# Candunio.net
KiCad netlist of a schematic drawn in Altium Designer
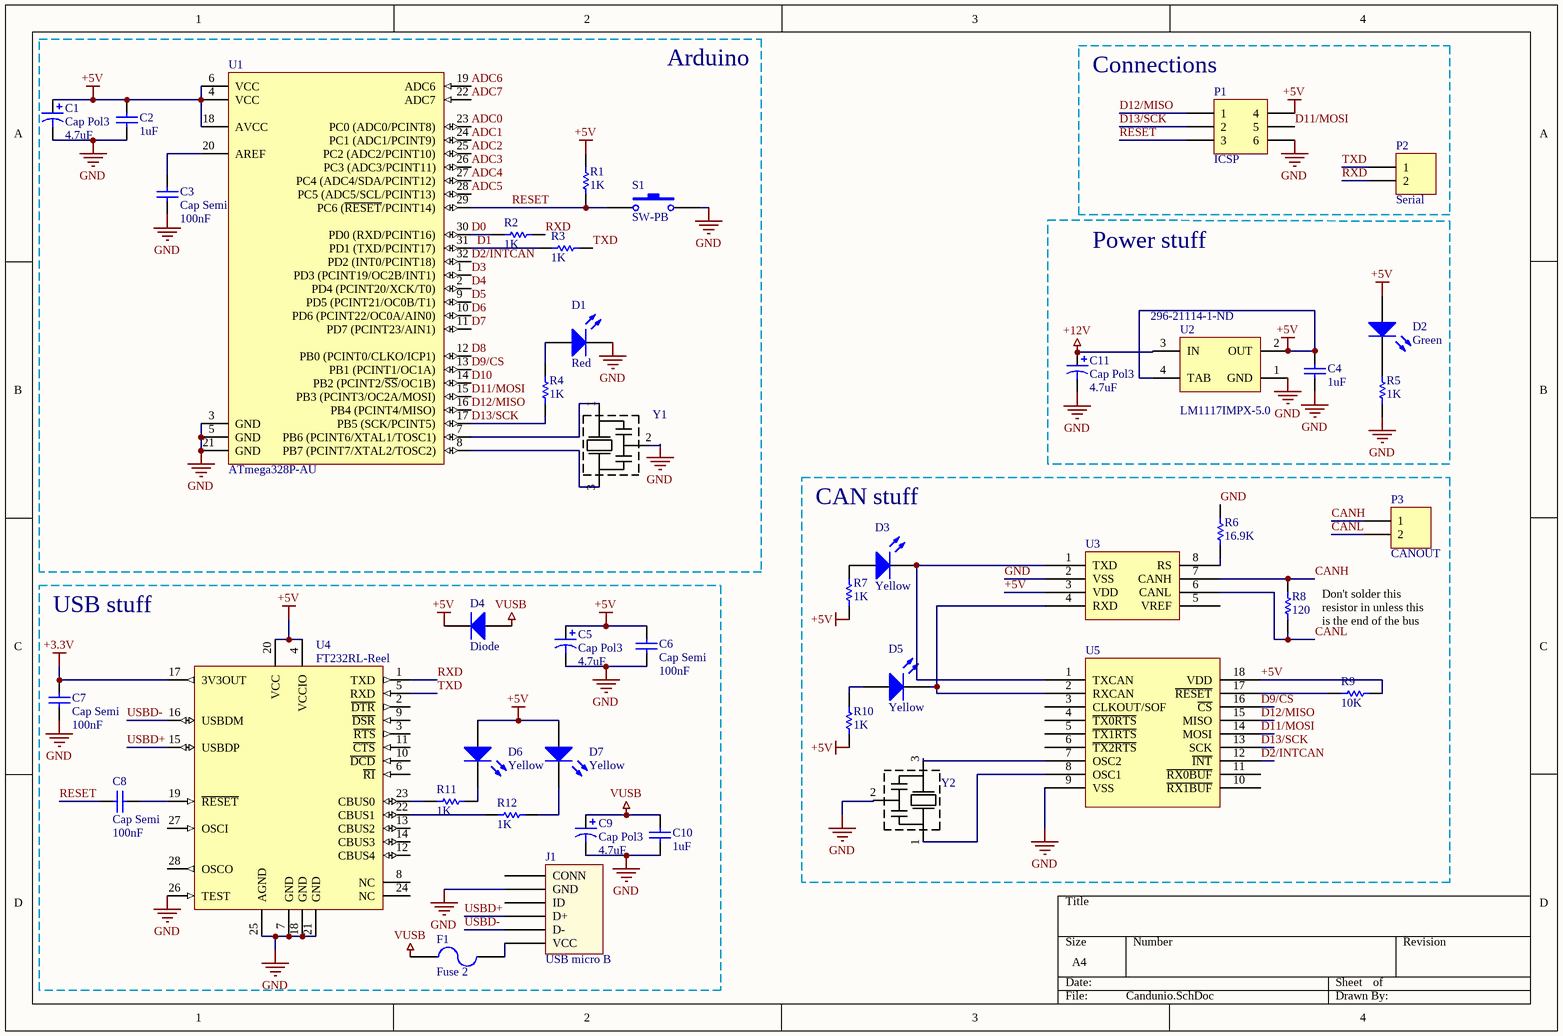
[diagram p0: Candunio.SchDoc]

(export (version "E")
  (design (tool "Eeschema 10.0.6"))
  (components
    (comp (ref "C1")
      (value "Cap Pol3")
      (footprint "CAPC3216X170N")
      (description "Polarized Capacitor (Surface Mount)")
      (fields
        (field (name "ALTIUM_VALUE") "4.7uF")
        (field (name "MANUFACTURER") "Kyocera AVX")
        (field (name "MANUFACTURER PART NUMBER") "12063C475KAT2A")
        (field (name "PUBLISHER") "Altium Limited")
      )
      (libsource (lib "Miscellaneous Devices") (part "Cap Pol3"))
    )
    (comp (ref "C2")
      (value "1uF")
      (footprint "CAPC3216X170N")
      (description "Capacitor (Semiconductor SIM Model)")
      (fields
        (field (name "MANUFACTURER") "Murata")
        (field (name "MANUFACTURER PART NUMBER") "GRM31MR71H105KA88L")
        (field (name "PUBLISHER") "Altium Limited")
      )
      (libsource (lib "Miscellaneous Devices") (part "Cap Semi"))
    )
    (comp (ref "C3")
      (value "Cap Semi")
      (footprint "CAPC3216X170N")
      (description "Capacitor (Semiconductor SIM Model)")
      (fields
        (field (name "ALTIUM_VALUE") "100nF")
        (field (name "MANUFACTURER") "Yageo")
        (field (name "MANUFACTURER PART NUMBER") "CC1206KKX7R0BB104")
        (field (name "PUBLISHER") "Altium Limited")
      )
      (libsource (lib "Miscellaneous Devices") (part "Cap Semi"))
    )
    (comp (ref "C4")
      (value "1uF")
      (footprint "CAPC3216X170N")
      (description "Capacitor (Semiconductor SIM Model)")
      (fields
        (field (name "MANUFACTURER") "Murata")
        (field (name "MANUFACTURER PART NUMBER") "GRM31MR71H105KA88L")
        (field (name "PUBLISHER") "Altium Limited")
      )
      (libsource (lib "Miscellaneous Devices") (part "Cap Semi"))
    )
    (comp (ref "C5")
      (value "Cap Pol3")
      (footprint "CAPC3216X170N")
      (description "Polarized Capacitor (Surface Mount)")
      (fields
        (field (name "ALTIUM_VALUE") "4.7uF")
        (field (name "MANUFACTURER") "Kyocera AVX")
        (field (name "MANUFACTURER PART NUMBER") "12063C475KAT2A")
        (field (name "PUBLISHER") "Altium Limited")
      )
      (libsource (lib "Miscellaneous Devices") (part "Cap Pol3"))
    )
    (comp (ref "C6")
      (value "Cap Semi")
      (footprint "CAPC3216X170N")
      (description "Capacitor (Semiconductor SIM Model)")
      (fields
        (field (name "ALTIUM_VALUE") "100nF")
        (field (name "MANUFACTURER") "Yageo")
        (field (name "MANUFACTURER PART NUMBER") "CC1206KKX7R0BB104")
        (field (name "PUBLISHER") "Altium Limited")
      )
      (libsource (lib "Miscellaneous Devices") (part "Cap Semi"))
    )
    (comp (ref "C7")
      (value "Cap Semi")
      (footprint "CAPC3216X170N")
      (description "Capacitor (Semiconductor SIM Model)")
      (fields
        (field (name "ALTIUM_VALUE") "100nF")
        (field (name "MANUFACTURER") "Yageo")
        (field (name "MANUFACTURER PART NUMBER") "CC1206KKX7R0BB104")
        (field (name "PUBLISHER") "Altium Limited")
      )
      (libsource (lib "Miscellaneous Devices") (part "Cap Semi"))
    )
    (comp (ref "C8")
      (value "Cap Semi")
      (footprint "CAPC3216X170N")
      (description "Capacitor (Semiconductor SIM Model)")
      (fields
        (field (name "ALTIUM_VALUE") "100nF")
        (field (name "MANUFACTURER") "Yageo")
        (field (name "MANUFACTURER PART NUMBER") "CC1206KKX7R0BB104")
        (field (name "PUBLISHER") "Altium Limited")
      )
      (libsource (lib "Miscellaneous Devices") (part "Cap Semi"))
    )
    (comp (ref "C9")
      (value "Cap Pol3")
      (footprint "CAPC3216X170N")
      (description "Polarized Capacitor (Surface Mount)")
      (fields
        (field (name "ALTIUM_VALUE") "4.7uF")
        (field (name "MANUFACTURER") "Kyocera AVX")
        (field (name "MANUFACTURER PART NUMBER") "12063C475KAT2A")
        (field (name "PUBLISHER") "Altium Limited")
      )
      (libsource (lib "Miscellaneous Devices") (part "Cap Pol3"))
    )
    (comp (ref "C10")
      (value "1uF")
      (footprint "CAPC3216X170N")
      (description "Capacitor (Semiconductor SIM Model)")
      (fields
        (field (name "MANUFACTURER") "Murata")
        (field (name "MANUFACTURER PART NUMBER") "GRM31MR71H105KA88L")
        (field (name "PUBLISHER") "Altium Limited")
      )
      (libsource (lib "Miscellaneous Devices") (part "Cap Semi"))
    )
    (comp (ref "C11")
      (value "Cap Pol3")
      (footprint "CAPC3216X170N")
      (description "Polarized Capacitor (Surface Mount)")
      (fields
        (field (name "ALTIUM_VALUE") "4.7uF")
        (field (name "MANUFACTURER") "Kyocera AVX")
        (field (name "MANUFACTURER PART NUMBER") "12063C475KAT2A")
        (field (name "PUBLISHER") "Altium Limited")
      )
      (libsource (lib "Miscellaneous Devices") (part "Cap Pol3"))
    )
    (comp (ref "D1")
      (value "Red")
      (footprint "LEDC3216X120NRED")
      (description "Typical RED, GREEN, YELLOW, AMBER GaAs LED")
      (fields
        (field (name "MANUFACTURER") "Broadcom Avago")
        (field (name "MANUFACTURER PART NUMBER") "HSMY-C150")
        (field (name "PUBLISHER") "Altium Limited")
      )
      (libsource (lib "Miscellaneous Devices") (part "LED2"))
    )
    (comp (ref "D2")
      (value "Green")
      (footprint "LEDC3216X120NGRN")
      (description "Typical RED, GREEN, YELLOW, AMBER GaAs LED")
      (fields
        (field (name "MANUFACTURER") "Broadcom Avago")
        (field (name "MANUFACTURER PART NUMBER") "HSMG-C150")
        (field (name "PUBLISHER") "Altium Limited")
      )
      (libsource (lib "Miscellaneous Devices") (part "LED2"))
    )
    (comp (ref "D3")
      (value "Yellow")
      (footprint "LEDC3216X120NYEL")
      (description "Typical RED, GREEN, YELLOW, AMBER GaAs LED")
      (fields
        (field (name "MANUFACTURER") "Broadcom Avago")
        (field (name "MANUFACTURER PART NUMBER") "HSMY-C150")
        (field (name "PUBLISHER") "Altium Limited")
      )
      (libsource (lib "Miscellaneous Devices") (part "LED2"))
    )
    (comp (ref "D4")
      (value "Diode")
      (footprint "DO-220AA")
      (description "Default Diode")
      (fields (field (name "PUBLISHER") "Altium Limited"))
      (libsource (lib "Miscellaneous Devices") (part "Diode"))
    )
    (comp (ref "D5")
      (value "Yellow")
      (footprint "LEDC3216X120NYEL")
      (description "Typical RED, GREEN, YELLOW, AMBER GaAs LED")
      (fields
        (field (name "MANUFACTURER") "Broadcom Avago")
        (field (name "MANUFACTURER PART NUMBER") "HSMY-C150")
        (field (name "PUBLISHER") "Altium Limited")
      )
      (libsource (lib "Miscellaneous Devices") (part "LED2"))
    )
    (comp (ref "D6")
      (value "Yellow")
      (footprint "LEDC3216X120NYEL")
      (description "Typical RED, GREEN, YELLOW, AMBER GaAs LED")
      (fields
        (field (name "MANUFACTURER") "Broadcom Avago")
        (field (name "MANUFACTURER PART NUMBER") "HSMY-C150")
        (field (name "PUBLISHER") "Altium Limited")
      )
      (libsource (lib "Miscellaneous Devices") (part "LED2"))
    )
    (comp (ref "D7")
      (value "Yellow")
      (footprint "LEDC3216X120NYEL")
      (description "Typical RED, GREEN, YELLOW, AMBER GaAs LED")
      (fields
        (field (name "MANUFACTURER") "Broadcom Avago")
        (field (name "MANUFACTURER PART NUMBER") "HSMY-C150")
        (field (name "PUBLISHER") "Altium Limited")
      )
      (libsource (lib "Miscellaneous Devices") (part "LED2"))
    )
    (comp (ref "F1")
      (value "Fuse 2")
      (footprint "FUSC4632X85N")
      (description "Fuse")
      (fields
        (field (name "PART NUMBER") "MF-MSMF050-2")
        (field (name "MANUFACTURER") "Bourns")
        (field (name "PUBLISHER") "Altium Limited")
      )
      (libsource (lib "Miscellaneous Devices") (part "Fuse 2"))
    )
    (comp (ref "J1")
      (value "USB micro B")
      (footprint "1050170001")
      (description "CONN SM TH USB MICRO MODIFIED FOR DRILL")
      (fields (field (name "PART NUMBER") "WM1399CT-ND"))
      (libsource (lib "electronpowered") (part "1050170001"))
    )
    (comp (ref "P1")
      (value "ICSP")
      (footprint "Pin Header 2x3 TH Pitch 2.54mm")
      (description "Header, 3-Pin, Dual row")
      (fields (field (name "PUBLISHER") "Altium Limited"))
      (libsource (lib "Miscellaneous Connectors") (part "Header 3X2A"))
    )
    (comp (ref "P2")
      (value "Serial")
      (footprint "Candunio v2018_7_16:Pin Header 1x2 TH Pitch 2.54mm")
      (description "Header, 2-Pin")
      (fields (field (name "PUBLISHER") "Altium Limited"))
      (libsource (lib "Miscellaneous Connectors") (part "Header 2"))
    )
    (comp (ref "P3")
      (value "CANOUT")
      (footprint "Candunio v2018_7_16:Pin Header 1x2 TH Pitch 2.54mm")
      (description "Header, 2-Pin")
      (fields (field (name "PUBLISHER") "Altium Limited"))
      (libsource (lib "Miscellaneous Connectors") (part "Header 2"))
    )
    (comp (ref "R1")
      (value "1K")
      (footprint "RESC3216X60N")
      (description "Resistor")
      (fields
        (field (name "MANUFACTURER") "Stackpole Electronics")
        (field (name "MANUFACTURER PART NUMBER") "RNCP1206FTD1K00")
      )
      (libsource (lib "Miscellaneous Devices") (part "Res1"))
    )
    (comp (ref "R2")
      (value "1K")
      (footprint "RESC3216X60N")
      (description "Resistor")
      (fields
        (field (name "MANUFACTURER") "Stackpole Electronics")
        (field (name "MANUFACTURER PART NUMBER") "RNCP1206FTD1K00")
      )
      (libsource (lib "Miscellaneous Devices") (part "Res1"))
    )
    (comp (ref "R3")
      (value "1K")
      (footprint "RESC3216X60N")
      (description "Resistor")
      (fields
        (field (name "MANUFACTURER") "Stackpole Electronics")
        (field (name "MANUFACTURER PART NUMBER") "RNCP1206FTD1K00")
      )
      (libsource (lib "Miscellaneous Devices") (part "Res1"))
    )
    (comp (ref "R4")
      (value "1K")
      (footprint "RESC3216X60N")
      (description "Resistor")
      (fields
        (field (name "MANUFACTURER") "Stackpole Electronics")
        (field (name "MANUFACTURER PART NUMBER") "RNCP1206FTD1K00")
      )
      (libsource (lib "Miscellaneous Devices") (part "Res1"))
    )
    (comp (ref "R5")
      (value "1K")
      (footprint "RESC3216X60N")
      (description "Resistor")
      (fields
        (field (name "MANUFACTURER") "Stackpole Electronics")
        (field (name "MANUFACTURER PART NUMBER") "RNCP1206FTD1K00")
      )
      (libsource (lib "Miscellaneous Devices") (part "Res1"))
    )
    (comp (ref "R6")
      (value "16.9K")
      (footprint "RESC3216X60N")
      (description "Resistor")
      (fields
        (field (name "MANUFACTURER") "TE Connectivity Holsworthy")
        (field (name "MANUFACTURER PART NUMBER") "CRGH1206F16K9")
      )
      (libsource (lib "Miscellaneous Devices") (part "Res1"))
    )
    (comp (ref "R7")
      (value "1K")
      (footprint "RESC3216X60N")
      (description "Resistor")
      (fields
        (field (name "MANUFACTURER") "Stackpole Electronics")
        (field (name "MANUFACTURER PART NUMBER") "RNCP1206FTD1K00")
      )
      (libsource (lib "Miscellaneous Devices") (part "Res1"))
    )
    (comp (ref "R8")
      (value "120")
      (footprint "RESC3216X60N")
      (description "Resistor")
      (fields
        (field (name "MANUFACTURER") "Vishay")
        (field (name "MANUFACTURER PART NUMBER") "CRCW1206120RFKEAHP")
      )
      (libsource (lib "Miscellaneous Devices") (part "Res1"))
    )
    (comp (ref "R9")
      (value "10K")
      (footprint "RESC3216X60N")
      (description "Resistor")
      (fields
        (field (name "MANUFACTURER") "Stackpole Electronics")
        (field (name "MANUFACTURER PART NUMBER") "RNCP1206FTD10K0")
      )
      (libsource (lib "Miscellaneous Devices") (part "Res1"))
    )
    (comp (ref "R10")
      (value "1K")
      (footprint "RESC3216X60N")
      (description "Resistor")
      (fields
        (field (name "MANUFACTURER") "Stackpole Electronics")
        (field (name "MANUFACTURER PART NUMBER") "RNCP1206FTD1K00")
      )
      (libsource (lib "Miscellaneous Devices") (part "Res1"))
    )
    (comp (ref "R11")
      (value "1K")
      (footprint "RESC3216X60N")
      (description "Resistor")
      (fields
        (field (name "MANUFACTURER") "Stackpole Electronics")
        (field (name "MANUFACTURER PART NUMBER") "RNCP1206FTD1K00")
      )
      (libsource (lib "Miscellaneous Devices") (part "Res1"))
    )
    (comp (ref "R12")
      (value "1K")
      (footprint "RESC3216X60N")
      (description "Resistor")
      (fields
        (field (name "MANUFACTURER") "Stackpole Electronics")
        (field (name "MANUFACTURER PART NUMBER") "RNCP1206FTD1K00")
      )
      (libsource (lib "Miscellaneous Devices") (part "Res1"))
    )
    (comp (ref "S1")
      (value "SW-PB")
      (footprint "C1206")
      (description "Switch")
      (fields
        (field (name "MANUFACTURER") "ITT C&K")
        (field (name "MANUFACTURER PART NUMBER") "KXT331LHS")
        (field (name "PUBLISHER") "Altium Limited")
      )
      (libsource (lib "Miscellaneous Devices") (part "SW-PB"))
    )
    (comp (ref "U1")
      (value "ATmega328P-AU")
      (footprint "QFP80P900X900X120-32N")
      (fields (field (name "PUBLISHER") "Altium Limited"))
      (libsource (lib "Atmel Microcontroller 8-Bit megaAVR") (part "ATmega328P-AU"))
    )
    (comp (ref "U2")
      (value "LM1117IMPX-5.0")
      (footprint "SOT230P700X180-4N")
      (description "800mA Low-Dropout Linear Regulator, 4-pin SOT-223")
      (fields
        (field (name "PARTNUMBER") "LM1117IMPX-5.0/NOPBCT-ND")
        (field (name "MANUFACTURER") "National Semiconductor")
        (field (name "SUPPLIER PART NUMBER") "296-21114-1-ND")
        (field (name "PUBLISHER") "Altium Limited")
      )
      (libsource (lib "NSC LDO") (part "LM1117IMPX-5.0"))
    )
    (comp (ref "U3")
      (value "MCP2551-E/SN")
      (footprint "SOIC127P600X175-8N")
      (description "SOIC")
      (libsource (lib "AMSComponents") (part "MCP2551-E/SN"))
    )
    (comp (ref "U4")
      (value "FT232RL-Reel")
      (footprint "SOP65P780X200-28N")
      (description "USB UART Asynchronous Serial Data Transfer Chip, SSOP-28, Tape and Reel")
      (fields
        (field (name "MANUFACTURER") "FTDI")
        (field (name "MANUFACTURER PART NUMBER") "FT232RL-REEL")
        (field (name "PUBLISHER") "Altium Limited")
      )
      (libsource (lib "FTDI Communication UART") (part "FT232RL-Reel"))
    )
    (comp (ref "U5")
      (value "MCP2515-E/ST")
      (footprint "SOIC127P1030X265-18N")
      (description "SOIC")
      (libsource (lib "AMSComponents") (part "MCP2515-E/ST"))
    )
    (comp (ref "Y1")
      (value "CSTCE16M0V53-R0")
      (footprint "Integrated_Library1:CSTCE_G")
      (fields
        (field (name "MANUFACTURER") "Murata")
        (field (name "MANUFACTURER PART NUMBER") "CSTCE16M0V53C-R0")
        (field (name "TOLERANCE") "0.5%")
      )
      (libsource (lib "AMSComponents") (part "CSTCE16M0V53-R0"))
    )
    (comp (ref "Y2")
      (value "CSTCE16M0V53-R0")
      (footprint "Integrated_Library1:CSTCE_G")
      (fields
        (field (name "MANUFACTURER") "Murata")
        (field (name "MANUFACTURER PART NUMBER") "CSTCE16M0V53C-R0")
        (field (name "TOLERANCE") "0.5%")
      )
      (libsource (lib "AMSComponents") (part "CSTCE16M0V53-R0"))
    )
  )
  (nets
    (net (code "1") (name "+3.3V") (class "Default")
      (node (ref "C7") (pin "1") (pinfunction "1_1") (pintype "passive"))
      (node (ref "U4") (pin "17") (pinfunction "3V3OUT_17") (pintype "output"))
    )
    (net (code "2") (name "+5V") (class "Default")
      (node (ref "C1") (pin "1") (pinfunction "1_1") (pintype "passive"))
      (node (ref "C2") (pin "1") (pinfunction "1_1") (pintype "passive"))
      (node (ref "C4") (pin "1") (pinfunction "1_1") (pintype "passive"))
      (node (ref "C5") (pin "1") (pinfunction "1_1") (pintype "passive"))
      (node (ref "C6") (pin "1") (pinfunction "1_1") (pintype "passive"))
      (node (ref "D2") (pin "1") (pinfunction "A_1") (pintype "passive"))
      (node (ref "D4") (pin "2") (pinfunction "K_2") (pintype "passive"))
      (node (ref "D6") (pin "1") (pinfunction "A_1") (pintype "passive"))
      (node (ref "D7") (pin "1") (pinfunction "A_1") (pintype "passive"))
      (node (ref "P1") (pin "4") (pinfunction "4_4") (pintype "passive"))
      (node (ref "R1") (pin "1") (pinfunction "1_1") (pintype "passive"))
      (node (ref "R10") (pin "2") (pinfunction "2_2") (pintype "passive"))
      (node (ref "R7") (pin "1") (pinfunction "1_1") (pintype "passive"))
      (node (ref "R9") (pin "2") (pinfunction "2_2") (pintype "passive"))
      (node (ref "U1") (pin "18") (pinfunction "AVCC_18") (pintype "power_in"))
      (node (ref "U1") (pin "4") (pinfunction "VCC_4") (pintype "power_in"))
      (node (ref "U1") (pin "6") (pinfunction "VCC_6") (pintype "power_in"))
      (node (ref "U2") (pin "2") (pinfunction "OUT_2") (pintype "power_in"))
      (node (ref "U2") (pin "4") (pinfunction "TAB_4") (pintype "power_in"))
      (node (ref "U3") (pin "3") (pinfunction "VDD_3") (pintype "passive"))
      (node (ref "U4") (pin "20") (pinfunction "VCC_20") (pintype "power_in"))
      (node (ref "U4") (pin "4") (pinfunction "VCCIO_4") (pintype "power_in"))
      (node (ref "U5") (pin "18") (pinfunction "VDD_18") (pintype "passive"))
    )
    (net (code "3") (name "+12V") (class "Default")
      (node (ref "C11") (pin "1") (pinfunction "1_1") (pintype "passive"))
      (node (ref "U2") (pin "3") (pinfunction "IN_3") (pintype "power_in"))
    )
    (net (code "4") (name "/ADC0") (class "Default")
      (node (ref "U1") (pin "23") (pinfunction "PC0_(ADC0/PCINT8)_23") (pintype "bidirectional"))
    )
    (net (code "5") (name "/ADC1") (class "Default")
      (node (ref "U1") (pin "24") (pinfunction "PC1_(ADC1/PCINT9)_24") (pintype "bidirectional"))
    )
    (net (code "6") (name "/ADC2") (class "Default")
      (node (ref "U1") (pin "25") (pinfunction "PC2_(ADC2/PCINT10)_25") (pintype "bidirectional"))
    )
    (net (code "7") (name "/ADC3") (class "Default")
      (node (ref "U1") (pin "26") (pinfunction "PC3_(ADC3/PCINT11)_26") (pintype "bidirectional"))
    )
    (net (code "8") (name "/ADC4") (class "Default")
      (node (ref "U1") (pin "27") (pinfunction "PC4_(ADC4/SDA/PCINT12)_27") (pintype "bidirectional"))
    )
    (net (code "9") (name "/ADC5") (class "Default")
      (node (ref "U1") (pin "28") (pinfunction "PC5_(ADC5/SCL/PCINT13)_28") (pintype "bidirectional"))
    )
    (net (code "10") (name "/ADC6") (class "Default")
      (node (ref "U1") (pin "19") (pinfunction "ADC6_19") (pintype "input"))
    )
    (net (code "11") (name "/ADC7") (class "Default")
      (node (ref "U1") (pin "22") (pinfunction "ADC7_22") (pintype "input"))
    )
    (net (code "12") (name "/CANH") (class "Default")
      (node (ref "P3") (pin "1") (pinfunction "1_1") (pintype "passive"))
      (node (ref "R8") (pin "1") (pinfunction "1_1") (pintype "passive"))
      (node (ref "U3") (pin "7") (pinfunction "CANH_7") (pintype "passive"))
    )
    (net (code "13") (name "/CANL") (class "Default")
      (node (ref "P3") (pin "2") (pinfunction "2_2") (pintype "passive"))
      (node (ref "R8") (pin "2") (pinfunction "2_2") (pintype "passive"))
      (node (ref "U3") (pin "6") (pinfunction "CANL_6") (pintype "passive"))
    )
    (net (code "14") (name "/D0") (class "Default")
      (node (ref "R2") (pin "1") (pinfunction "1_1") (pintype "passive"))
      (node (ref "U1") (pin "30") (pinfunction "PD0_(RXD/PCINT16)_30") (pintype "bidirectional"))
    )
    (net (code "15") (name "/D1") (class "Default")
      (node (ref "R3") (pin "1") (pinfunction "1_1") (pintype "passive"))
      (node (ref "U1") (pin "31") (pinfunction "PD1_(TXD/PCINT17)_31") (pintype "bidirectional"))
    )
    (net (code "16") (name "/D2{slash}INTCAN") (class "Default")
      (node (ref "U1") (pin "32") (pinfunction "PD2_(INT0/PCINT18)_32") (pintype "bidirectional"))
      (node (ref "U5") (pin "12") (pinfunction "~{INT}_12") (pintype "passive"))
    )
    (net (code "17") (name "/D3") (class "Default")
      (node (ref "U1") (pin "1") (pinfunction "PD3_(PCINT19/OC2B/INT1)_1") (pintype "bidirectional"))
    )
    (net (code "18") (name "/D4") (class "Default")
      (node (ref "U1") (pin "2") (pinfunction "PD4_(PCINT20/XCK/T0)_2") (pintype "bidirectional"))
    )
    (net (code "19") (name "/D5") (class "Default")
      (node (ref "U1") (pin "9") (pinfunction "PD5_(PCINT21/OC0B/T1)_9") (pintype "bidirectional"))
    )
    (net (code "20") (name "/D6") (class "Default")
      (node (ref "U1") (pin "10") (pinfunction "PD6_(PCINT22/OC0A/AIN0)_10") (pintype "bidirectional"))
    )
    (net (code "21") (name "/D7") (class "Default")
      (node (ref "U1") (pin "11") (pinfunction "PD7_(PCINT23/AIN1)_11") (pintype "bidirectional"))
    )
    (net (code "22") (name "/D8") (class "Default")
      (node (ref "U1") (pin "12") (pinfunction "PB0_(PCINT0/CLKO/ICP1)_12") (pintype "bidirectional"))
    )
    (net (code "23") (name "/D9{slash}CS") (class "Default")
      (node (ref "U1") (pin "13") (pinfunction "PB1_(PCINT1/OC1A)_13") (pintype "bidirectional"))
      (node (ref "U5") (pin "16") (pinfunction "~{CS}_16") (pintype "passive"))
    )
    (net (code "24") (name "/D10") (class "Default")
      (node (ref "U1") (pin "14") (pinfunction "PB2_(PCINT2/~{SS}/OC1B)_14") (pintype "bidirectional"))
    )
    (net (code "25") (name "/D11{slash}MOSI") (class "Default")
      (node (ref "P1") (pin "5") (pinfunction "5_5") (pintype "passive"))
      (node (ref "U1") (pin "15") (pinfunction "PB3_(PCINT3/OC2A/MOSI)_15") (pintype "bidirectional"))
      (node (ref "U5") (pin "14") (pinfunction "MOSI_14") (pintype "passive"))
    )
    (net (code "26") (name "/D12{slash}MISO") (class "Default")
      (node (ref "P1") (pin "1") (pinfunction "1_1") (pintype "passive"))
      (node (ref "U1") (pin "16") (pinfunction "PB4_(PCINT4/MISO)_16") (pintype "bidirectional"))
      (node (ref "U5") (pin "15") (pinfunction "MISO_15") (pintype "passive"))
    )
    (net (code "27") (name "/D13{slash}SCK") (class "Default")
      (node (ref "P1") (pin "2") (pinfunction "2_2") (pintype "passive"))
      (node (ref "R4") (pin "2") (pinfunction "2_2") (pintype "passive"))
      (node (ref "U1") (pin "17") (pinfunction "PB5_(SCK/PCINT5)_17") (pintype "bidirectional"))
      (node (ref "U5") (pin "13") (pinfunction "SCK_13") (pintype "passive"))
    )
    (net (code "28") (name "/RESET") (class "Default")
      (node (ref "C8") (pin "1") (pinfunction "1_1") (pintype "passive"))
      (node (ref "P1") (pin "3") (pinfunction "3_3") (pintype "passive"))
      (node (ref "R1") (pin "2") (pinfunction "2_2") (pintype "passive"))
      (node (ref "S1") (pin "1") (pinfunction "1_1") (pintype "passive"))
      (node (ref "U1") (pin "29") (pinfunction "PC6_(~{RESET}/PCINT14)_29") (pintype "bidirectional"))
    )
    (net (code "29") (name "/RXD") (class "Default")
      (node (ref "P2") (pin "2") (pinfunction "2_2") (pintype "passive"))
      (node (ref "R2") (pin "2") (pinfunction "2_2") (pintype "passive"))
      (node (ref "U4") (pin "1") (pinfunction "TXD_1") (pintype "output"))
    )
    (net (code "30") (name "/TXD") (class "Default")
      (node (ref "P2") (pin "1") (pinfunction "1_1") (pintype "passive"))
      (node (ref "R3") (pin "2") (pinfunction "2_2") (pintype "passive"))
      (node (ref "U4") (pin "5") (pinfunction "RXD_5") (pintype "input"))
    )
    (net (code "31") (name "/USBD+") (class "Default")
      (node (ref "J1") (pin "3") (pinfunction "D+_3") (pintype "passive"))
      (node (ref "U4") (pin "15") (pinfunction "USBDP_15") (pintype "bidirectional"))
    )
    (net (code "32") (name "/USBD-") (class "Default")
      (node (ref "J1") (pin "2") (pinfunction "D-_2") (pintype "passive"))
      (node (ref "U4") (pin "16") (pinfunction "USBDM_16") (pintype "bidirectional"))
    )
    (net (code "33") (name "GND") (class "Default")
      (node (ref "C1") (pin "2") (pinfunction "2_2") (pintype "passive"))
      (node (ref "C10") (pin "2") (pinfunction "2_2") (pintype "passive"))
      (node (ref "C11") (pin "2") (pinfunction "2_2") (pintype "passive"))
      (node (ref "C2") (pin "2") (pinfunction "2_2") (pintype "passive"))
      (node (ref "C3") (pin "2") (pinfunction "2_2") (pintype "passive"))
      (node (ref "C4") (pin "2") (pinfunction "2_2") (pintype "passive"))
      (node (ref "C5") (pin "2") (pinfunction "2_2") (pintype "passive"))
      (node (ref "C6") (pin "2") (pinfunction "2_2") (pintype "passive"))
      (node (ref "C7") (pin "2") (pinfunction "2_2") (pintype "passive"))
      (node (ref "C9") (pin "2") (pinfunction "2_2") (pintype "passive"))
      (node (ref "D1") (pin "2") (pinfunction "K_2") (pintype "passive"))
      (node (ref "J1") (pin "5") (pinfunction "GND_5") (pintype "passive"))
      (node (ref "P1") (pin "6") (pinfunction "6_6") (pintype "passive"))
      (node (ref "R5") (pin "2") (pinfunction "2_2") (pintype "passive"))
      (node (ref "R6") (pin "1") (pinfunction "1_1") (pintype "passive"))
      (node (ref "S1") (pin "2") (pinfunction "2_2") (pintype "passive"))
      (node (ref "U1") (pin "21") (pinfunction "GND_21") (pintype "power_in"))
      (node (ref "U1") (pin "3") (pinfunction "GND_3") (pintype "power_in"))
      (node (ref "U1") (pin "5") (pinfunction "GND_5") (pintype "power_in"))
      (node (ref "U2") (pin "1") (pinfunction "GND_1") (pintype "power_in"))
      (node (ref "U3") (pin "2") (pinfunction "VSS_2") (pintype "passive"))
      (node (ref "U4") (pin "18") (pinfunction "GND_18") (pintype "power_in"))
      (node (ref "U4") (pin "21") (pinfunction "GND_21") (pintype "power_in"))
      (node (ref "U4") (pin "25") (pinfunction "AGND_25") (pintype "power_in"))
      (node (ref "U4") (pin "26") (pinfunction "TEST_26") (pintype "input"))
      (node (ref "U4") (pin "7") (pinfunction "GND_7") (pintype "power_in"))
      (node (ref "U5") (pin "9") (pinfunction "VSS_9") (pintype "passive"))
      (node (ref "Y1") (pin "2") (pinfunction "2_2") (pintype "passive"))
      (node (ref "Y2") (pin "2") (pinfunction "2_2") (pintype "passive"))
    )
    (net (code "34") (name "Net-(D1-A)") (class "Default")
      (node (ref "D1") (pin "1") (pinfunction "A_1") (pintype "passive"))
      (node (ref "R4") (pin "1") (pinfunction "1_1") (pintype "passive"))
    )
    (net (code "35") (name "Net-(D2-K)") (class "Default")
      (node (ref "D2") (pin "2") (pinfunction "K_2") (pintype "passive"))
      (node (ref "R5") (pin "1") (pinfunction "1_1") (pintype "passive"))
    )
    (net (code "36") (name "Net-(D3-A)") (class "Default")
      (node (ref "D3") (pin "1") (pinfunction "A_1") (pintype "passive"))
      (node (ref "R7") (pin "2") (pinfunction "2_2") (pintype "passive"))
    )
    (net (code "37") (name "Net-(D3-K)") (class "Default")
      (node (ref "D3") (pin "2") (pinfunction "K_2") (pintype "passive"))
      (node (ref "U3") (pin "1") (pinfunction "TXD_1") (pintype "passive"))
      (node (ref "U5") (pin "1") (pinfunction "TXCAN_1") (pintype "passive"))
    )
    (net (code "38") (name "Net-(D5-A)") (class "Default")
      (node (ref "D5") (pin "1") (pinfunction "A_1") (pintype "passive"))
      (node (ref "R10") (pin "1") (pinfunction "1_1") (pintype "passive"))
    )
    (net (code "39") (name "Net-(D5-K)") (class "Default")
      (node (ref "D5") (pin "2") (pinfunction "K_2") (pintype "passive"))
      (node (ref "U3") (pin "4") (pinfunction "RXD_4") (pintype "passive"))
      (node (ref "U5") (pin "2") (pinfunction "RXCAN_2") (pintype "passive"))
    )
    (net (code "40") (name "Net-(D6-K)") (class "Default")
      (node (ref "D6") (pin "2") (pinfunction "K_2") (pintype "passive"))
      (node (ref "R11") (pin "2") (pinfunction "2_2") (pintype "passive"))
    )
    (net (code "41") (name "Net-(D7-K)") (class "Default")
      (node (ref "D7") (pin "2") (pinfunction "K_2") (pintype "passive"))
      (node (ref "R12") (pin "2") (pinfunction "2_2") (pintype "passive"))
    )
    (net (code "42") (name "Net-(J1-VCC)") (class "Default")
      (node (ref "F1") (pin "2") (pinfunction "2_2") (pintype "passive"))
      (node (ref "J1") (pin "1") (pinfunction "VCC_1") (pintype "passive"))
    )
    (net (code "43") (name "Net-(U1-AREF)") (class "Default")
      (node (ref "C3") (pin "1") (pinfunction "1_1") (pintype "passive"))
      (node (ref "U1") (pin "20") (pinfunction "AREF_20") (pintype "passive"))
    )
    (net (code "44") (name "Net-(U1-PB6_(PCINT6{slash}XTAL1{slash}TOSC1))") (class "Default")
      (node (ref "U1") (pin "7") (pinfunction "PB6_(PCINT6/XTAL1/TOSC1)_7") (pintype "bidirectional"))
      (node (ref "Y1") (pin "1") (pinfunction "1_1") (pintype "passive"))
    )
    (net (code "45") (name "Net-(U1-PB7_(PCINT7{slash}XTAL2{slash}TOSC2))") (class "Default")
      (node (ref "U1") (pin "8") (pinfunction "PB7_(PCINT7/XTAL2/TOSC2)_8") (pintype "bidirectional"))
      (node (ref "Y1") (pin "3") (pinfunction "3_3") (pintype "passive"))
    )
    (net (code "46") (name "Net-(U3-RS)") (class "Default")
      (node (ref "R6") (pin "2") (pinfunction "2_2") (pintype "passive"))
      (node (ref "U3") (pin "8") (pinfunction "RS_8") (pintype "passive"))
    )
    (net (code "47") (name "Net-(U4-CBUS0)") (class "Default")
      (node (ref "R11") (pin "1") (pinfunction "1_1") (pintype "passive"))
      (node (ref "U4") (pin "23") (pinfunction "CBUS0_23") (pintype "bidirectional"))
    )
    (net (code "48") (name "Net-(U4-CBUS1)") (class "Default")
      (node (ref "R12") (pin "1") (pinfunction "1_1") (pintype "passive"))
      (node (ref "U4") (pin "22") (pinfunction "CBUS1_22") (pintype "bidirectional"))
    )
    (net (code "49") (name "Net-(U4-~{RESET})") (class "Default")
      (node (ref "C8") (pin "2") (pinfunction "2_2") (pintype "passive"))
      (node (ref "U4") (pin "19") (pinfunction "~{RESET}_19") (pintype "input"))
    )
    (net (code "50") (name "Net-(U5-OSC1)") (class "Default")
      (node (ref "U5") (pin "8") (pinfunction "OSC1_8") (pintype "passive"))
      (node (ref "Y2") (pin "1") (pinfunction "1_1") (pintype "passive"))
    )
    (net (code "51") (name "Net-(U5-OSC2)") (class "Default")
      (node (ref "U5") (pin "7") (pinfunction "OSC2_7") (pintype "passive"))
      (node (ref "Y2") (pin "3") (pinfunction "3_3") (pintype "passive"))
    )
    (net (code "52") (name "Net-(U5-~{RESET})") (class "Default")
      (node (ref "R9") (pin "1") (pinfunction "1_1") (pintype "passive"))
      (node (ref "U5") (pin "17") (pinfunction "~{RESET}_17") (pintype "passive"))
    )
    (net (code "53") (name "VUSB") (class "Default")
      (node (ref "C10") (pin "1") (pinfunction "1_1") (pintype "passive"))
      (node (ref "C9") (pin "1") (pinfunction "1_1") (pintype "passive"))
      (node (ref "D4") (pin "1") (pinfunction "A_1") (pintype "passive"))
      (node (ref "F1") (pin "1") (pinfunction "1_1") (pintype "passive"))
    )
    (net (code "54") (name "unconnected-(J1-CONN-Pad0)") (class "Default")
      (node (ref "J1") (pin "0") (pinfunction "CONN_0") (pintype "passive"))
    )
    (net (code "55") (name "unconnected-(J1-ID-Pad4)") (class "Default")
      (node (ref "J1") (pin "4") (pinfunction "ID_4") (pintype "passive"))
    )
    (net (code "56") (name "unconnected-(U3-VREF-Pad5)") (class "Default")
      (node (ref "U3") (pin "5") (pinfunction "VREF_5") (pintype "passive"))
    )
    (net (code "57") (name "unconnected-(U4-CBUS2-Pad13)") (class "Default")
      (node (ref "U4") (pin "13") (pinfunction "CBUS2_13") (pintype "bidirectional"))
    )
    (net (code "58") (name "unconnected-(U4-CBUS3-Pad14)") (class "Default")
      (node (ref "U4") (pin "14") (pinfunction "CBUS3_14") (pintype "bidirectional"))
    )
    (net (code "59") (name "unconnected-(U4-CBUS4-Pad12)") (class "Default")
      (node (ref "U4") (pin "12") (pinfunction "CBUS4_12") (pintype "bidirectional"))
    )
    (net (code "60") (name "unconnected-(U4-NC-Pad8)") (class "Default")
      (node (ref "U4") (pin "8") (pinfunction "NC_8") (pintype "passive"))
    )
    (net (code "61") (name "unconnected-(U4-NC-Pad24)") (class "Default")
      (node (ref "U4") (pin "24") (pinfunction "NC_24") (pintype "passive"))
    )
    (net (code "62") (name "unconnected-(U4-OSCI-Pad27)") (class "Default")
      (node (ref "U4") (pin "27") (pinfunction "OSCI_27") (pintype "input"))
    )
    (net (code "63") (name "unconnected-(U4-OSCO-Pad28)") (class "Default")
      (node (ref "U4") (pin "28") (pinfunction "OSCO_28") (pintype "output"))
    )
    (net (code "64") (name "unconnected-(U4-~{CTS}-Pad11)") (class "Default")
      (node (ref "U4") (pin "11") (pinfunction "~{CTS}_11") (pintype "input"))
    )
    (net (code "65") (name "unconnected-(U4-~{DCD}-Pad10)") (class "Default")
      (node (ref "U4") (pin "10") (pinfunction "~{DCD}_10") (pintype "input"))
    )
    (net (code "66") (name "unconnected-(U4-~{DSR}-Pad9)") (class "Default")
      (node (ref "U4") (pin "9") (pinfunction "~{DSR}_9") (pintype "input"))
    )
    (net (code "67") (name "unconnected-(U4-~{DTR}-Pad2)") (class "Default")
      (node (ref "U4") (pin "2") (pinfunction "~{DTR}_2") (pintype "output"))
    )
    (net (code "68") (name "unconnected-(U4-~{RI}-Pad6)") (class "Default")
      (node (ref "U4") (pin "6") (pinfunction "~{RI}_6") (pintype "input"))
    )
    (net (code "69") (name "unconnected-(U4-~{RTS}-Pad3)") (class "Default")
      (node (ref "U4") (pin "3") (pinfunction "~{RTS}_3") (pintype "output"))
    )
    (net (code "70") (name "unconnected-(U5-CLKOUT{slash}SOF-Pad3)") (class "Default")
      (node (ref "U5") (pin "3") (pinfunction "CLKOUT/SOF_3") (pintype "passive"))
    )
    (net (code "71") (name "unconnected-(U5-~{RX0BUF}-Pad11)") (class "Default")
      (node (ref "U5") (pin "11") (pinfunction "~{RX0BUF}_11") (pintype "passive"))
    )
    (net (code "72") (name "unconnected-(U5-~{RX1BUF}-Pad10)") (class "Default")
      (node (ref "U5") (pin "10") (pinfunction "~{RX1BUF}_10") (pintype "passive"))
    )
    (net (code "73") (name "unconnected-(U5-~{TX0RTS}-Pad4)") (class "Default")
      (node (ref "U5") (pin "4") (pinfunction "~{TX0RTS}_4") (pintype "passive"))
    )
    (net (code "74") (name "unconnected-(U5-~{TX1RTS}-Pad5)") (class "Default")
      (node (ref "U5") (pin "5") (pinfunction "~{TX1RTS}_5") (pintype "passive"))
    )
    (net (code "75") (name "unconnected-(U5-~{TX2RTS}-Pad6)") (class "Default")
      (node (ref "U5") (pin "6") (pinfunction "~{TX2RTS}_6") (pintype "passive"))
    )
  )
)
